# Dell_Supply_Hack_V1_1.net
KiCad netlist of a schematic drawn in EAGLE
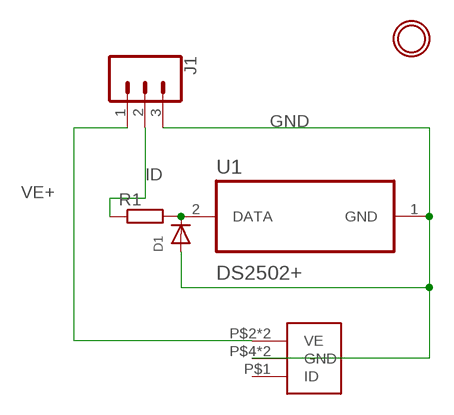
[diagram p0: schematic, sheet 1]

(export (version "E")
  (design (tool "Eeschema 10.0.6"))
  (components
    (comp (ref "D1")
      (value "DIODESOD-323F")
      (footprint "eagle-import:SOD-323F")
      (libsource (lib "eagle-import") (part "DIODESOD-323F"))
    )
    (comp (ref "J1")
      (value "CONN_03LONGPADS")
      (footprint "eagle-import:1X03_LONGPADS")
      (libsource (lib "eagle-import") (part "CONN_03LONGPADS"))
    )
    (comp (ref "R1")
      (value "R-EU_R0603")
      (footprint "eagle-import:R0603")
      (libsource (lib "eagle-import") (part "R-EU_R0603"))
    )
    (comp (ref "U$1")
      (value "DELL_CON")
      (footprint "eagle-import:DELL_CON_01")
      (libsource (lib "eagle-import") (part "DELL_CON"))
    )
    (comp (ref "U$2")
      (value "MOUNTING_HOLE")
      (footprint "eagle-import:MOUNTINGHOLE_3.0_PLATED")
      (libsource (lib "eagle-import") (part "MOUNTING_HOLE"))
    )
    (comp (ref "U1")
      (value "DS2502+")
      (footprint "eagle-import:TO92127P495H695-3")
      (fields (field (name "MF") "Maxim Integrated") (field (name "MP") "DS2502"))
      (libsource (lib "eagle-import") (part "DS2502+"))
    )
  )
  (nets
    (net (code "1") (name "/GND") (class "Default")
      (node (ref "D1") (pin "A") (pinfunction "A_A") (pintype "passive"))
      (node (ref "J1") (pin "3") (pinfunction "3_3") (pintype "passive"))
      (node (ref "U$1") (pin "P$4") (pinfunction "GND_P$4") (pintype "bidirectional"))
      (node (ref "U$1") (pin "P$5") (pinfunction "GND_P$5") (pintype "bidirectional"))
      (node (ref "U1") (pin "1") (pinfunction "GND_1") (pintype "power_in"))
    )
    (net (code "2") (name "/ID") (class "Default")
      (node (ref "J1") (pin "2") (pinfunction "2_2") (pintype "passive"))
      (node (ref "R1") (pin "1") (pinfunction "1_1") (pintype "passive"))
    )
    (net (code "3") (name "/VE+") (class "Default")
      (node (ref "J1") (pin "1") (pinfunction "1_1") (pintype "passive"))
      (node (ref "U$1") (pin "P$2") (pinfunction "VE_P$2") (pintype "bidirectional"))
      (node (ref "U$1") (pin "P$3") (pinfunction "VE_P$3") (pintype "bidirectional"))
    )
    (net (code "4") (name "Net-(U1-DATA)") (class "Default")
      (node (ref "D1") (pin "C") (pinfunction "C_C") (pintype "passive"))
      (node (ref "R1") (pin "2") (pinfunction "2_2") (pintype "passive"))
      (node (ref "U1") (pin "2") (pinfunction "DATA_2") (pintype "bidirectional"))
    )
    (net (code "5") (name "unconnected-(U$1-ID-PadP$1)") (class "Default")
      (node (ref "U$1") (pin "P$1") (pinfunction "ID_P$1") (pintype "bidirectional"))
    )
  )
)
